# TELM0002ADC.net
KiCad netlist of a schematic drawn in Altium Designer
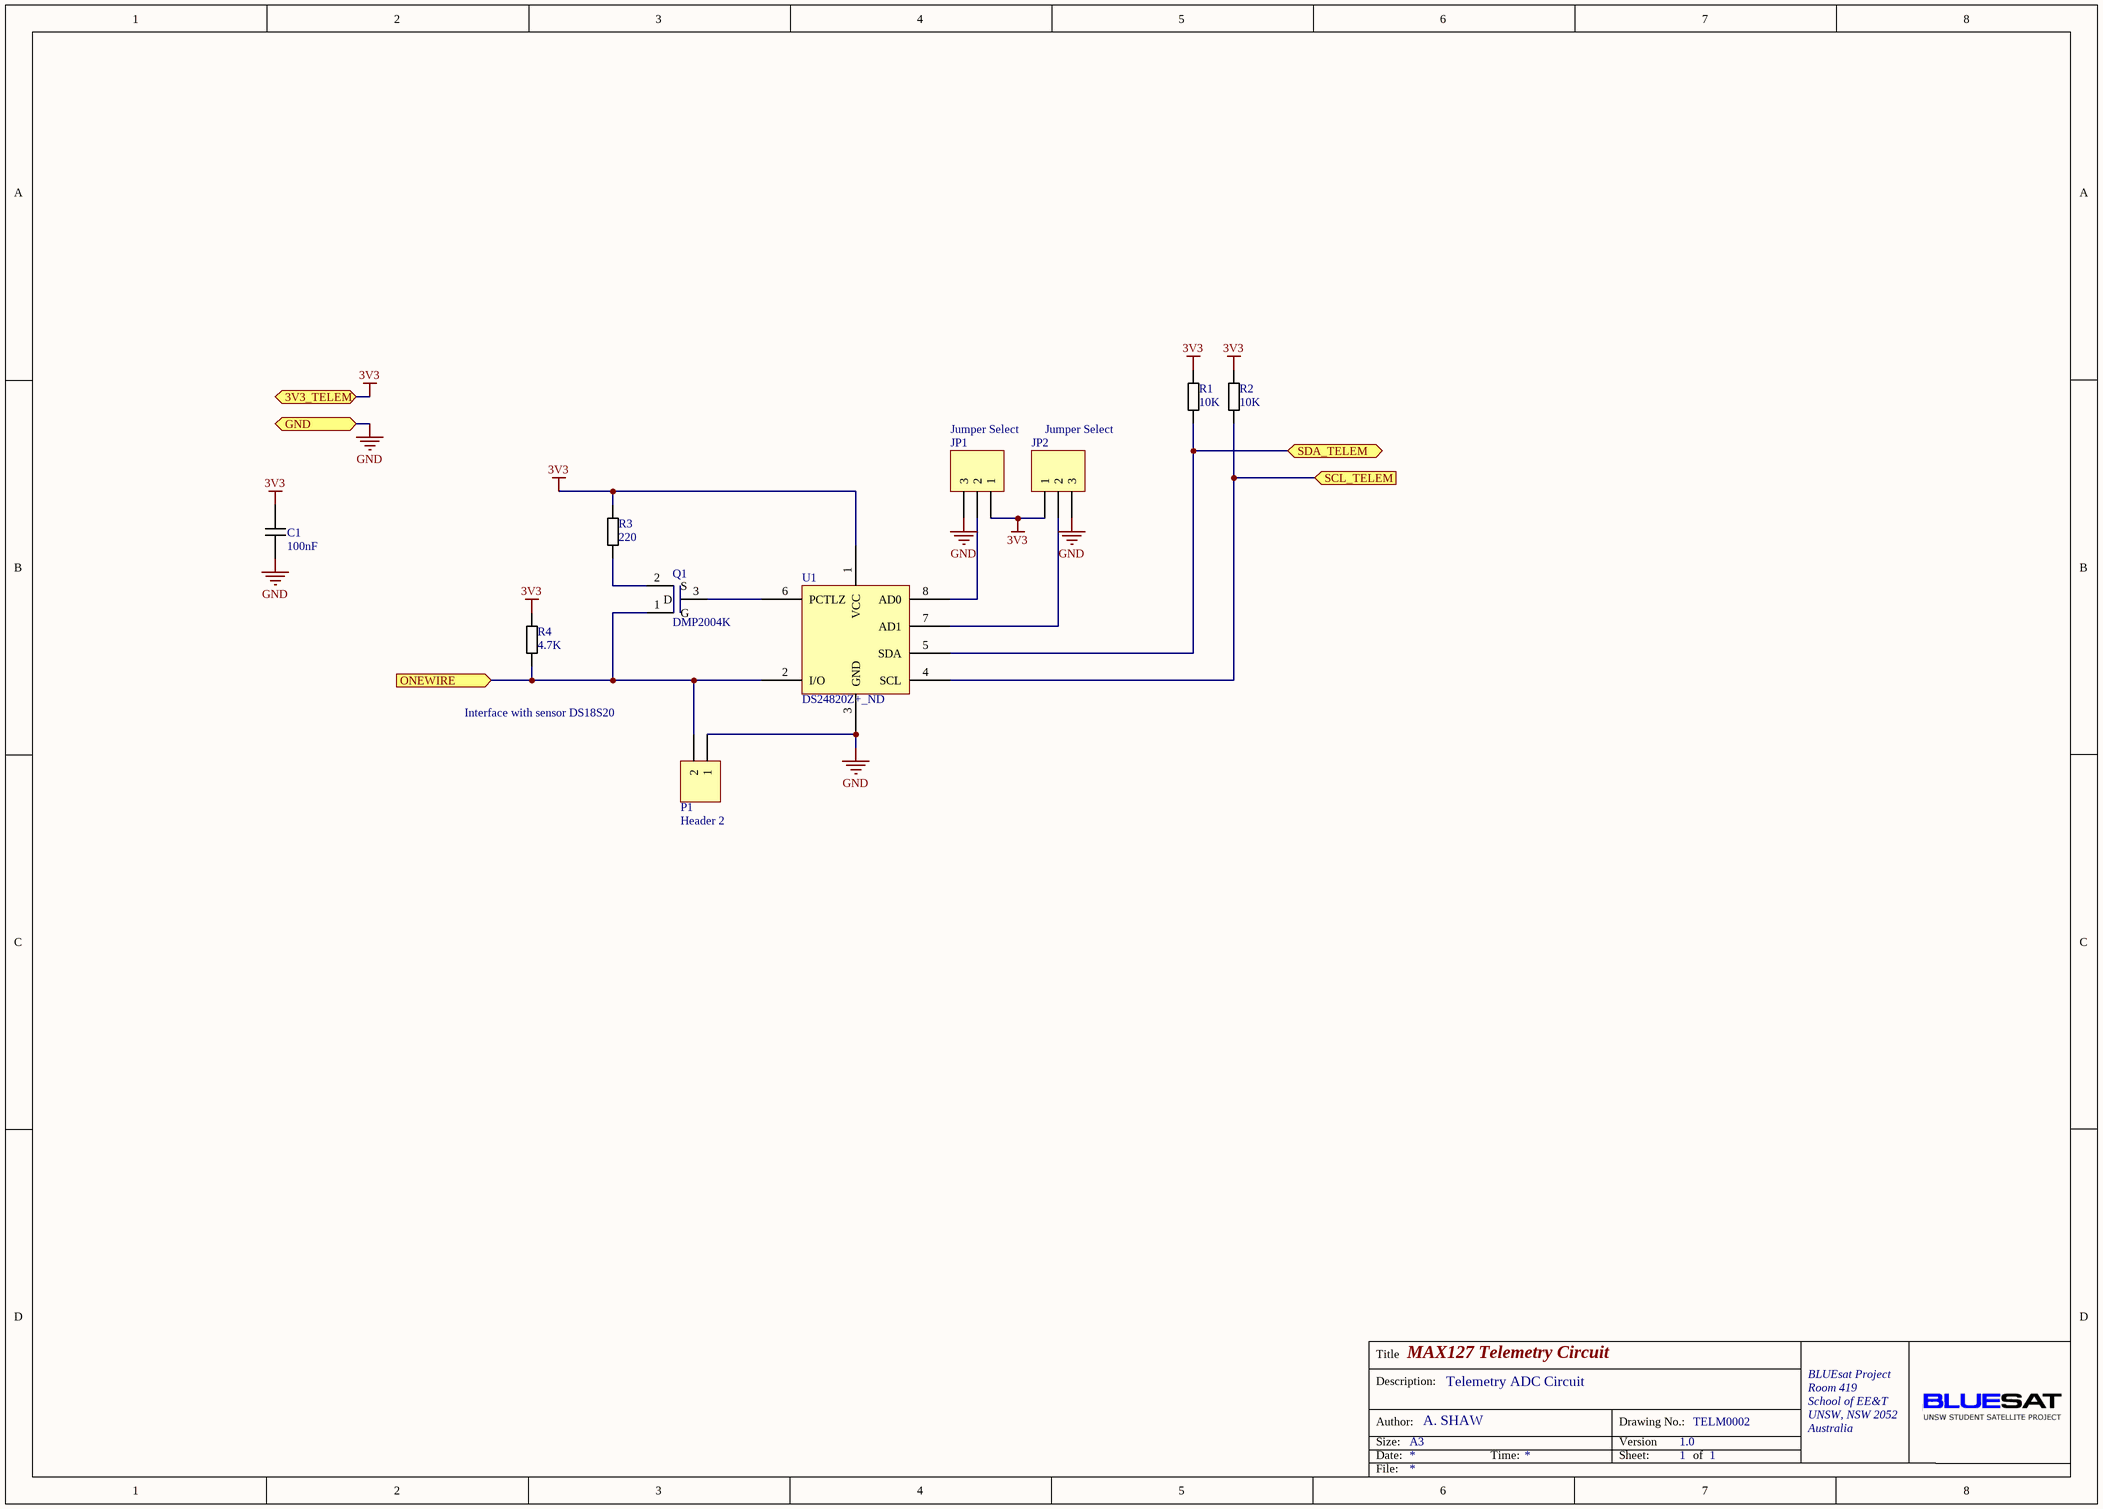
[diagram p0: TELM0002ADC.SchDoc]

(export (version "E")
  (design (tool "Eeschema 10.0.6"))
  (components
    (comp (ref "C1")
      (value "100nF")
      (footprint "0805 Cap")
      (description "0805 MLCC - X7R, 10%")
      (fields (field (name "Comment") "0805 Cap"))
      (libsource (lib "Schlib1") (part "0805 MLCC - X7R, 10%"))
    )
    (comp (ref "JP1")
      (value "Jumper Select")
      (footprint "SOLDER_JUMPER_3_A")
      (description "Header, 3-Pin")
      (libsource (lib "") (part "Header 3_1"))
    )
    (comp (ref "JP2")
      (value "Jumper Select")
      (footprint "SOLDER_JUMPER_3_A")
      (description "Header, 3-Pin")
      (libsource (lib "Miscellaneous Connectors") (part "Header 3"))
    )
    (comp (ref "P1")
      (value "Header 2")
      (footprint "HDR1X2")
      (description "Header, 2-Pin")
      (libsource (lib "Miscellaneous Connectors") (part "Header 2"))
    )
    (comp (ref "Q1")
      (value "DMP2004K")
      (footprint "DMP2004KDITR-ND")
      (description "MOSFET P-CH 20V 600MA SOT23-3")
      (libsource (lib "Telemetry") (part "DMP2004K"))
    )
    (comp (ref "R1")
      (value "10K")
      (footprint "0805 Resistor")
      (description "0805 Thick Film Resistor 1%")
      (fields (field (name "Comment") "0805 Resistor"))
      (libsource (lib "Schlib1") (part "0805 Thick Film Resistor 1%"))
    )
    (comp (ref "R2")
      (value "10K")
      (footprint "0805 Resistor")
      (description "0805 Thick Film Resistor 1%")
      (fields (field (name "Comment") "0805 Resistor"))
      (libsource (lib "Schlib1") (part "0805 Thick Film Resistor 1%"))
    )
    (comp (ref "R3")
      (value "220")
      (footprint "0805 Resistor")
      (description "0805 Thick Film Resistor 1%")
      (fields (field (name "Comment") "0805 Resistor"))
      (libsource (lib "Schlib1") (part "0805 Thick Film Resistor 1%"))
    )
    (comp (ref "R4")
      (value "4.7K")
      (footprint "0805 Resistor")
      (description "0603 Thick Film Resistor 1%")
      (fields (field (name "Comment") "0603 Resistor"))
      (libsource (lib "Schlib1") (part "0603 Thick Film Resistor 1%"))
    )
    (comp (ref "U1")
      (value "DS24820Z+_ND")
      (footprint "DS2482-100")
      (libsource (lib "Telemetry") (part "DS24820Z+_ND"))
    )
  )
  (nets
    (net (code "1") (name "/ONEWIRE") (class "Default")
      (node (ref "P1") (pin "2") (pinfunction "2_2") (pintype "passive"))
      (node (ref "Q1") (pin "1") (pinfunction "G_1") (pintype "passive"))
      (node (ref "R4") (pin "1") (pinfunction "1_1") (pintype "passive"))
      (node (ref "U1") (pin "2") (pinfunction "I/O_2") (pintype "passive"))
    )
    (net (code "2") (name "/SCL_TELEM") (class "Default")
      (node (ref "R2") (pin "1") (pinfunction "1_1") (pintype "passive"))
      (node (ref "U1") (pin "4") (pinfunction "SCL_4") (pintype "passive"))
    )
    (net (code "3") (name "/SDA_TELEM") (class "Default")
      (node (ref "R1") (pin "1") (pinfunction "1_1") (pintype "passive"))
      (node (ref "U1") (pin "5") (pinfunction "SDA_5") (pintype "passive"))
    )
    (net (code "4") (name "3V3") (class "Default")
      (node (ref "C1") (pin "2") (pinfunction "2_2") (pintype "passive"))
      (node (ref "JP1") (pin "1") (pinfunction "1_1") (pintype "passive"))
      (node (ref "JP2") (pin "1") (pinfunction "1_1") (pintype "passive"))
      (node (ref "R1") (pin "2") (pinfunction "2_2") (pintype "passive"))
      (node (ref "R2") (pin "2") (pinfunction "2_2") (pintype "passive"))
      (node (ref "R3") (pin "2") (pinfunction "2_2") (pintype "passive"))
      (node (ref "R4") (pin "2") (pinfunction "2_2") (pintype "passive"))
      (node (ref "U1") (pin "1") (pinfunction "VCC_1") (pintype "passive"))
    )
    (net (code "5") (name "GND") (class "Default")
      (node (ref "C1") (pin "1") (pinfunction "1_1") (pintype "passive"))
      (node (ref "JP1") (pin "3") (pinfunction "3_3") (pintype "passive"))
      (node (ref "JP2") (pin "3") (pinfunction "3_3") (pintype "passive"))
      (node (ref "P1") (pin "1") (pinfunction "1_1") (pintype "passive"))
      (node (ref "U1") (pin "3") (pinfunction "GND_3") (pintype "passive"))
    )
    (net (code "6") (name "Net-(Q1-D)") (class "Default")
      (node (ref "Q1") (pin "3") (pinfunction "D_3") (pintype "passive"))
      (node (ref "U1") (pin "6") (pinfunction "PCTLZ_6") (pintype "passive"))
    )
    (net (code "7") (name "Net-(Q1-S)") (class "Default")
      (node (ref "Q1") (pin "2") (pinfunction "S_2") (pintype "passive"))
      (node (ref "R3") (pin "1") (pinfunction "1_1") (pintype "passive"))
    )
    (net (code "8") (name "Net-(U1-AD0)") (class "Default")
      (node (ref "JP1") (pin "2") (pinfunction "2_2") (pintype "passive"))
      (node (ref "U1") (pin "8") (pinfunction "AD0_8") (pintype "passive"))
    )
    (net (code "9") (name "Net-(U1-AD1)") (class "Default")
      (node (ref "JP2") (pin "2") (pinfunction "2_2") (pintype "passive"))
      (node (ref "U1") (pin "7") (pinfunction "AD1_7") (pintype "passive"))
    )
  )
)
